# touch-24-v4.net
KiCad netlist of a schematic drawn in Altium Designer
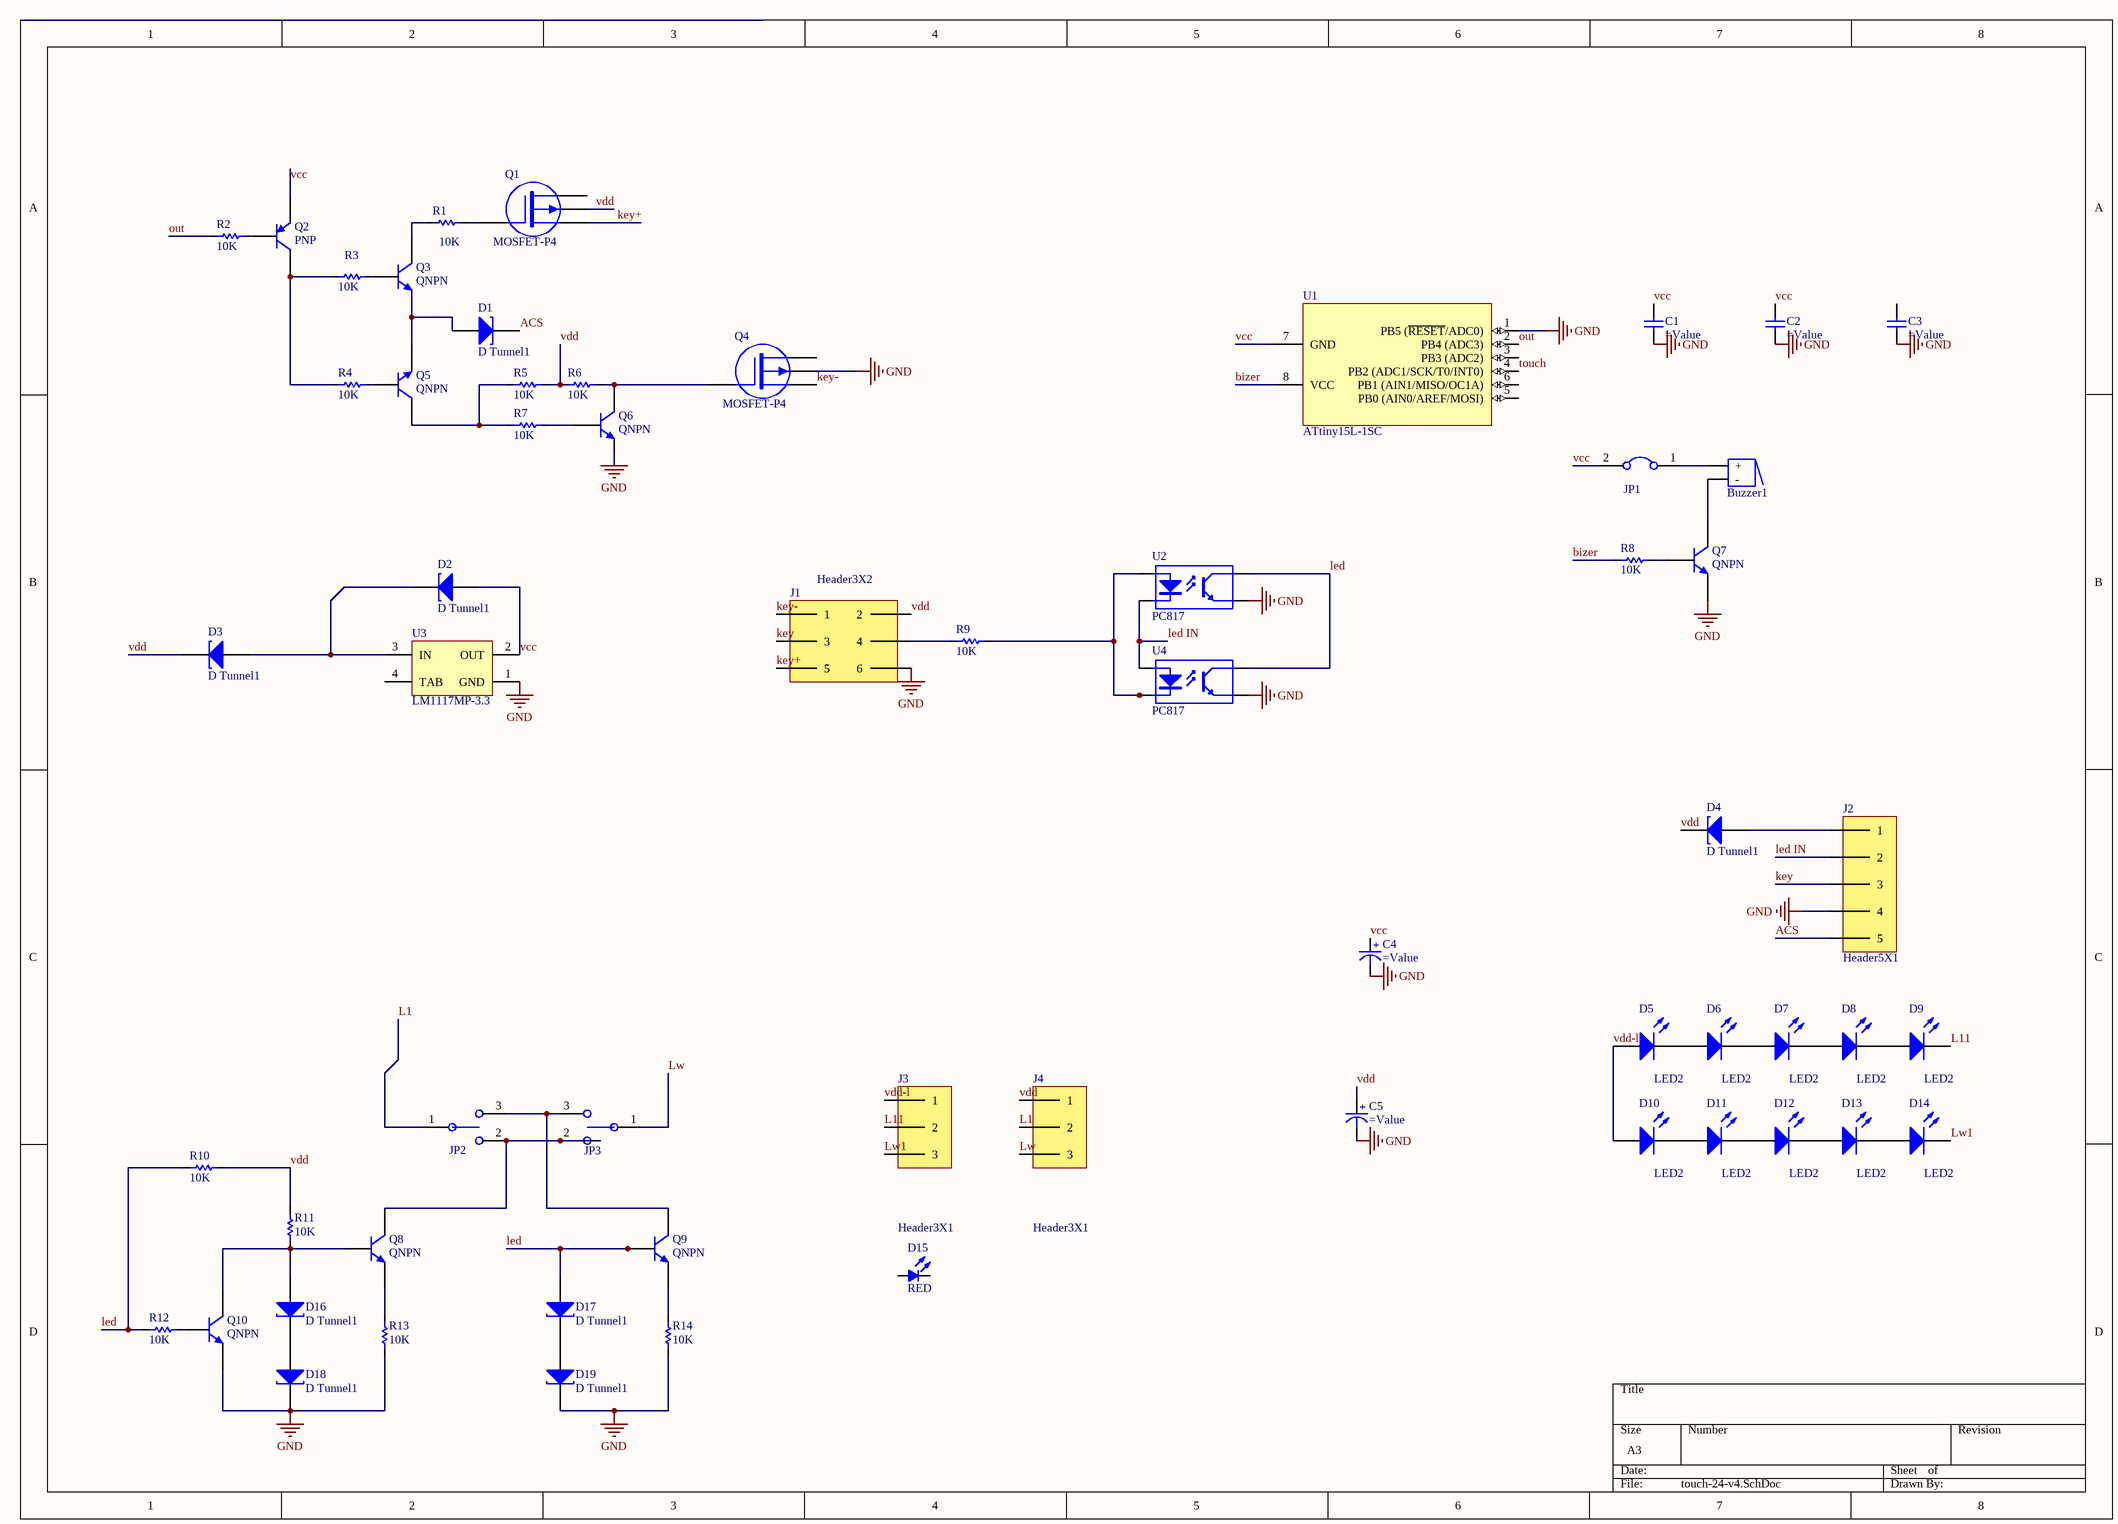
[diagram p0: touch-24-v4.SchDoc]

(export (version "E")
  (design (tool "Eeschema 10.0.6"))
  (components
    (comp (ref "Buzzer1")
      (value "Buzzer")
      (footprint "BUZZER")
      (fields (field (name "DESIGNER") "Seyed Mohsen Ghasemain"))
      (libsource (lib "PicPars.com_usefully_Library") (part "Buzzer"))
    )
    (comp (ref "C1")
      (value "~")
      (footprint "CAP 1206")
      (description "Capacitor")
      (libsource (lib "AltiumLib1") (part "Capacitor"))
    )
    (comp (ref "C2")
      (value "~")
      (footprint "CAP 1206")
      (description "Capacitor")
      (libsource (lib "AltiumLib1") (part "Capacitor"))
    )
    (comp (ref "C3")
      (value "~")
      (footprint "CAP 1206")
      (description "Capacitor")
      (libsource (lib "AltiumLib1") (part "Capacitor"))
    )
    (comp (ref "C4")
      (value "~")
      (footprint "ELEC-CAP-RAD10-20")
      (description "Electrolytic Capacitor")
      (libsource (lib "AltiumLib1") (part "Capacitor Electrolytic"))
    )
    (comp (ref "C5")
      (value "~")
      (footprint "ELEC-CAP-RAD15-30")
      (description "Electrolytic Capacitor")
      (libsource (lib "AltiumLib1") (part "Capacitor Electrolytic"))
    )
    (comp (ref "D1")
      (value "D Tunnel1")
      (footprint "3.2X1.6X1.1")
      (description "Tunnel Diode - RLC Model")
      (fields (field (name "PUBLISHER") "Altium Limited"))
      (libsource (lib "Miscellaneous Devices") (part "D Tunnel1"))
    )
    (comp (ref "D2")
      (value "D Tunnel1")
      (footprint "3.2X1.6X1.1")
      (description "Tunnel Diode - RLC Model")
      (fields (field (name "PUBLISHER") "Altium Limited"))
      (libsource (lib "Miscellaneous Devices") (part "D Tunnel1"))
    )
    (comp (ref "D3")
      (value "D Tunnel1")
      (footprint "3.2X1.6X1.1")
      (description "Tunnel Diode - RLC Model")
      (fields (field (name "PUBLISHER") "Altium Limited"))
      (libsource (lib "Miscellaneous Devices") (part "D Tunnel1"))
    )
    (comp (ref "D4")
      (value "D Tunnel1")
      (footprint "3.2X1.6X1.1")
      (description "Tunnel Diode - RLC Model")
      (fields (field (name "PUBLISHER") "Altium Limited"))
      (libsource (lib "Miscellaneous Devices") (part "D Tunnel1"))
    )
    (comp (ref "D5")
      (value "LED2")
      (footprint "3.2X1.6X1.1")
      (description "Typical RED, GREEN, YELLOW, AMBER GaAs LED")
      (fields (field (name "PUBLISHER") "Altium Limited"))
      (libsource (lib "Miscellaneous Devices") (part "LED2"))
    )
    (comp (ref "D6")
      (value "LED2")
      (footprint "3.2X1.6X1.1")
      (description "Typical RED, GREEN, YELLOW, AMBER GaAs LED")
      (fields (field (name "PUBLISHER") "Altium Limited"))
      (libsource (lib "Miscellaneous Devices") (part "LED2"))
    )
    (comp (ref "D7")
      (value "LED2")
      (footprint "3.2X1.6X1.1")
      (description "Typical RED, GREEN, YELLOW, AMBER GaAs LED")
      (fields (field (name "PUBLISHER") "Altium Limited"))
      (libsource (lib "Miscellaneous Devices") (part "LED2"))
    )
    (comp (ref "D8")
      (value "LED2")
      (footprint "3.2X1.6X1.1")
      (description "Typical RED, GREEN, YELLOW, AMBER GaAs LED")
      (fields (field (name "PUBLISHER") "Altium Limited"))
      (libsource (lib "Miscellaneous Devices") (part "LED2"))
    )
    (comp (ref "D9")
      (value "LED2")
      (footprint "3.2X1.6X1.1")
      (description "Typical RED, GREEN, YELLOW, AMBER GaAs LED")
      (fields (field (name "PUBLISHER") "Altium Limited"))
      (libsource (lib "Miscellaneous Devices") (part "LED2"))
    )
    (comp (ref "D10")
      (value "LED2")
      (footprint "3.2X1.6X1.1")
      (description "Typical RED, GREEN, YELLOW, AMBER GaAs LED")
      (fields (field (name "PUBLISHER") "Altium Limited"))
      (libsource (lib "Miscellaneous Devices") (part "LED2"))
    )
    (comp (ref "D11")
      (value "LED2")
      (footprint "3.2X1.6X1.1")
      (description "Typical RED, GREEN, YELLOW, AMBER GaAs LED")
      (fields (field (name "PUBLISHER") "Altium Limited"))
      (libsource (lib "Miscellaneous Devices") (part "LED2"))
    )
    (comp (ref "D12")
      (value "LED2")
      (footprint "3.2X1.6X1.1")
      (description "Typical RED, GREEN, YELLOW, AMBER GaAs LED")
      (fields (field (name "PUBLISHER") "Altium Limited"))
      (libsource (lib "Miscellaneous Devices") (part "LED2"))
    )
    (comp (ref "D13")
      (value "LED2")
      (footprint "3.2X1.6X1.1")
      (description "Typical RED, GREEN, YELLOW, AMBER GaAs LED")
      (fields (field (name "PUBLISHER") "Altium Limited"))
      (libsource (lib "Miscellaneous Devices") (part "LED2"))
    )
    (comp (ref "D14")
      (value "LED2")
      (footprint "3.2X1.6X1.1")
      (description "Typical RED, GREEN, YELLOW, AMBER GaAs LED")
      (fields (field (name "PUBLISHER") "Altium Limited"))
      (libsource (lib "Miscellaneous Devices") (part "LED2"))
    )
    (comp (ref "D15")
      (value "MODEL")
      (footprint "RES 0805 (2012X06L)")
      (description "Typical LED")
      (fields (field (name "COLOR") "RED"))
      (libsource (lib "AltiumLib1") (part "LED 5mm"))
    )
    (comp (ref "D16")
      (value "D Tunnel1")
      (footprint "3.2X1.6X1.1")
      (description "Tunnel Diode - RLC Model")
      (fields (field (name "PUBLISHER") "Altium Limited"))
      (libsource (lib "Miscellaneous Devices") (part "D Tunnel1"))
    )
    (comp (ref "D17")
      (value "D Tunnel1")
      (footprint "3.2X1.6X1.1")
      (description "Tunnel Diode - RLC Model")
      (fields (field (name "PUBLISHER") "Altium Limited"))
      (libsource (lib "Miscellaneous Devices") (part "D Tunnel1"))
    )
    (comp (ref "D18")
      (value "D Tunnel1")
      (footprint "3.2X1.6X1.1")
      (description "Tunnel Diode - RLC Model")
      (fields (field (name "PUBLISHER") "Altium Limited"))
      (libsource (lib "Miscellaneous Devices") (part "D Tunnel1"))
    )
    (comp (ref "D19")
      (value "D Tunnel1")
      (footprint "3.2X1.6X1.1")
      (description "Tunnel Diode - RLC Model")
      (fields (field (name "PUBLISHER") "Altium Limited"))
      (libsource (lib "Miscellaneous Devices") (part "D Tunnel1"))
    )
    (comp (ref "J1")
      (value "Header3X2")
      (footprint "HEADER 3X2")
      (libsource (lib "AltiumLib1") (part "Header3X2"))
    )
    (comp (ref "J2")
      (value "Header5X1")
      (footprint "HEADER 5X1")
      (libsource (lib "AltiumLib1") (part "Header5X1"))
    )
    (comp (ref "J3")
      (value "Header3X1")
      (footprint "HEADER 3X1")
      (libsource (lib "AltiumLib1") (part "Header3X1"))
    )
    (comp (ref "J4")
      (value "Header3X1")
      (footprint "HEADER 3X1")
      (libsource (lib "AltiumLib1") (part "Header3X1"))
    )
    (comp (ref "JP1")
      (value "Jumper")
      (footprint "Header 2X1")
      (libsource (lib "AltiumLib1") (part "Jumper"))
    )
    (comp (ref "JP2")
      (value "Jumper Selector")
      (footprint "Jumper Selector")
      (libsource (lib "AltiumLib1") (part "Jumper Selector"))
    )
    (comp (ref "JP3")
      (value "Jumper Selector")
      (footprint "Jumper Selector")
      (libsource (lib "") (part "Jumper Selector_1"))
    )
    (comp (ref "Q1")
      (value "MOSFET-P4")
      (footprint "SOT223_N")
      (description "P-Channel MOSFET, Externally Terminated Substrate")
      (fields (field (name "PUBLISHER") "Altium Limited"))
      (libsource (lib "Miscellaneous Devices") (part "MOSFET-P4"))
    )
    (comp (ref "Q2")
      (value "PNP")
      (footprint "SOT-23B_N")
      (description "PNP Bipolar Transistor")
      (fields (field (name "PUBLISHER") "Altium Limited"))
      (libsource (lib "Miscellaneous Devices") (part "PNP"))
    )
    (comp (ref "Q3")
      (value "QNPN")
      (footprint "SOT-23B_L")
      (description "NPN Bipolar Transistor")
      (fields (field (name "PUBLISHER") "Altium Limited"))
      (libsource (lib "Miscellaneous Devices") (part "QNPN"))
    )
    (comp (ref "Q4")
      (value "MOSFET-P4")
      (footprint "SOT223_N")
      (description "P-Channel MOSFET, Externally Terminated Substrate")
      (fields (field (name "PUBLISHER") "Altium Limited"))
      (libsource (lib "Miscellaneous Devices") (part "MOSFET-P4"))
    )
    (comp (ref "Q5")
      (value "QNPN")
      (footprint "SOT-23B_L")
      (description "NPN Bipolar Transistor")
      (fields (field (name "PUBLISHER") "Altium Limited"))
      (libsource (lib "Miscellaneous Devices") (part "QNPN"))
    )
    (comp (ref "Q6")
      (value "QNPN")
      (footprint "SOT-23B_L")
      (description "NPN Bipolar Transistor")
      (fields (field (name "PUBLISHER") "Altium Limited"))
      (libsource (lib "Miscellaneous Devices") (part "QNPN"))
    )
    (comp (ref "Q7")
      (value "QNPN")
      (footprint "SOT-23B_L")
      (description "NPN Bipolar Transistor")
      (fields (field (name "PUBLISHER") "Altium Limited"))
      (libsource (lib "Miscellaneous Devices") (part "QNPN"))
    )
    (comp (ref "Q8")
      (value "QNPN")
      (footprint "SOT-23B_L")
      (description "NPN Bipolar Transistor")
      (fields (field (name "PUBLISHER") "Altium Limited"))
      (libsource (lib "Miscellaneous Devices") (part "QNPN"))
    )
    (comp (ref "Q9")
      (value "QNPN")
      (footprint "SOT-23B_L")
      (description "NPN Bipolar Transistor")
      (fields (field (name "PUBLISHER") "Altium Limited"))
      (libsource (lib "Miscellaneous Devices") (part "QNPN"))
    )
    (comp (ref "Q10")
      (value "QNPN")
      (footprint "SOT-23B_L")
      (description "NPN Bipolar Transistor")
      (fields (field (name "PUBLISHER") "Altium Limited"))
      (libsource (lib "Miscellaneous Devices") (part "QNPN"))
    )
    (comp (ref "R1")
      (value "10K")
      (footprint "RES 1206 (3216X08L)")
      (description "Resistor")
      (fields (field (name "TOLERANCE") "5%") (field (name "POWER") "1/4 W"))
      (libsource (lib "AltiumLib1") (part "Resistor"))
    )
    (comp (ref "R2")
      (value "10K")
      (footprint "RES 1206 (3216X08L)")
      (description "Resistor")
      (fields (field (name "TOLERANCE") "5%") (field (name "POWER") "1/4 W"))
      (libsource (lib "AltiumLib1") (part "Resistor"))
    )
    (comp (ref "R3")
      (value "10K")
      (footprint "RES 1206 (3216X08L)")
      (description "Resistor")
      (fields (field (name "TOLERANCE") "5%") (field (name "POWER") "1/4 W"))
      (libsource (lib "AltiumLib1") (part "Resistor"))
    )
    (comp (ref "R4")
      (value "10K")
      (footprint "RES 1206 (3216X08L)")
      (description "Resistor")
      (fields (field (name "TOLERANCE") "5%") (field (name "POWER") "1/4 W"))
      (libsource (lib "AltiumLib1") (part "Resistor"))
    )
    (comp (ref "R5")
      (value "10K")
      (footprint "RES 1206 (3216X08L)")
      (description "Resistor")
      (fields (field (name "TOLERANCE") "5%") (field (name "POWER") "1/4 W"))
      (libsource (lib "AltiumLib1") (part "Resistor"))
    )
    (comp (ref "R6")
      (value "10K")
      (footprint "RES 1206 (3216X08L)")
      (description "Resistor")
      (fields (field (name "TOLERANCE") "5%") (field (name "POWER") "1/4 W"))
      (libsource (lib "AltiumLib1") (part "Resistor"))
    )
    (comp (ref "R7")
      (value "10K")
      (footprint "RES 1206 (3216X08L)")
      (description "Resistor")
      (fields (field (name "TOLERANCE") "5%") (field (name "POWER") "1/4 W"))
      (libsource (lib "AltiumLib1") (part "Resistor"))
    )
    (comp (ref "R8")
      (value "10K")
      (footprint "RES 1206 (3216X08L)")
      (description "Resistor")
      (fields (field (name "TOLERANCE") "5%") (field (name "POWER") "1/4 W"))
      (libsource (lib "AltiumLib1") (part "Resistor"))
    )
    (comp (ref "R9")
      (value "10K")
      (footprint "RES 1206 (3216X08L)")
      (description "Resistor")
      (fields (field (name "TOLERANCE") "5%") (field (name "POWER") "1/4 W"))
      (libsource (lib "AltiumLib1") (part "Resistor"))
    )
    (comp (ref "R10")
      (value "10K")
      (footprint "RES 1206 (3216X08L)")
      (description "Resistor")
      (fields (field (name "TOLERANCE") "5%") (field (name "POWER") "1/4 W"))
      (libsource (lib "AltiumLib1") (part "Resistor"))
    )
    (comp (ref "R11")
      (value "10K")
      (footprint "RES 1206 (3216X08L)")
      (description "Resistor")
      (fields (field (name "TOLERANCE") "5%") (field (name "POWER") "1/4 W"))
      (libsource (lib "AltiumLib1") (part "Resistor"))
    )
    (comp (ref "R12")
      (value "10K")
      (footprint "RES 1206 (3216X08L)")
      (description "Resistor")
      (fields (field (name "TOLERANCE") "5%") (field (name "POWER") "1/4 W"))
      (libsource (lib "AltiumLib1") (part "Resistor"))
    )
    (comp (ref "R13")
      (value "10K")
      (footprint "RES 1206 (3216X08L)")
      (description "Resistor")
      (fields (field (name "TOLERANCE") "5%") (field (name "POWER") "1/4 W"))
      (libsource (lib "AltiumLib1") (part "Resistor"))
    )
    (comp (ref "R14")
      (value "10K")
      (footprint "RES 1206 (3216X08L)")
      (description "Resistor")
      (fields (field (name "TOLERANCE") "5%") (field (name "POWER") "1/4 W"))
      (libsource (lib "AltiumLib1") (part "Resistor"))
    )
    (comp (ref "U1")
      (value "ATtiny15L-1SC")
      (footprint "8S2_N")
      (description "8-Bit AVR Microcontroller with 1K Byte of Flash Memory")
      (fields (field (name "PUBLISHER") "Altium Limited"))
      (libsource (lib "Atmel Microcontroller 8-Bit AVR") (part "ATtiny15L-1SC"))
    )
    (comp (ref "U2")
      (value "PC817")
      (footprint "DIP4")
      (description "4-Pin Phototransistor Optocoupler")
      (libsource (lib "AltiumLib1") (part "OPTCOUPLER_01"))
    )
    (comp (ref "U3")
      (value "LM1117MP-3.3")
      (footprint "Miscellaneous Devices:SOT89L")
      (description "800mA Low-Dropout Linear Regulator")
      (fields
        (field (name "MANUFACTURER") "National Semiconductor")
        (field (name "DIGIKEYPARTNUMBER") "LM1117MP-3.3CT-ND")
        (field (name "PUBLISHER") "Altium Limited")
      )
      (libsource (lib "NSC LDO") (part "LM1117MP-3.3"))
    )
    (comp (ref "U4")
      (value "PC817")
      (footprint "DIP4")
      (description "4-Pin Phototransistor Optocoupler")
      (libsource (lib "AltiumLib1") (part "OPTCOUPLER_01"))
    )
  )
  (nets
    (net (code "1") (name "/ACS") (class "Default")
      (node (ref "D1") (pin "2") (pinfunction "K_2") (pintype "passive"))
      (node (ref "J2") (pin "5") (pinfunction "5_5") (pintype "passive"))
    )
    (net (code "2") (name "/L1") (class "Default")
      (node (ref "J4") (pin "2") (pinfunction "2_2") (pintype "passive"))
      (node (ref "JP2") (pin "1") (pinfunction "1_1") (pintype "passive"))
    )
    (net (code "3") (name "/L11") (class "Default")
      (node (ref "D9") (pin "2") (pinfunction "K_2") (pintype "passive"))
      (node (ref "J3") (pin "2") (pinfunction "2_2") (pintype "passive"))
    )
    (net (code "4") (name "/Lw") (class "Default")
      (node (ref "J4") (pin "3") (pinfunction "3_3") (pintype "passive"))
      (node (ref "JP3") (pin "1") (pinfunction "1_1") (pintype "passive"))
    )
    (net (code "5") (name "/Lw1") (class "Default")
      (node (ref "D14") (pin "2") (pinfunction "K_2") (pintype "passive"))
      (node (ref "J3") (pin "3") (pinfunction "3_3") (pintype "passive"))
    )
    (net (code "6") (name "/bizer") (class "Default")
      (node (ref "R8") (pin "1") (pinfunction "1_1") (pintype "passive"))
      (node (ref "U1") (pin "8") (pinfunction "VCC_8") (pintype "power_in"))
    )
    (net (code "7") (name "/key") (class "Default")
      (node (ref "J1") (pin "3") (pinfunction "3_3") (pintype "passive"))
      (node (ref "J2") (pin "3") (pinfunction "3_3") (pintype "passive"))
    )
    (net (code "8") (name "/key+") (class "Default")
      (node (ref "J1") (pin "5") (pinfunction "5_5") (pintype "passive"))
      (node (ref "Q1") (pin "4") (pinfunction "S_4") (pintype "passive"))
    )
    (net (code "9") (name "/key-") (class "Default")
      (node (ref "J1") (pin "1") (pinfunction "1_1") (pintype "passive"))
      (node (ref "Q4") (pin "4") (pinfunction "S_4") (pintype "passive"))
    )
    (net (code "10") (name "/led") (class "Default")
      (node (ref "D17") (pin "1") (pinfunction "A_1") (pintype "passive"))
      (node (ref "Q9") (pin "2") (pinfunction "B_2") (pintype "passive"))
      (node (ref "R10") (pin "1") (pinfunction "1_1") (pintype "passive"))
      (node (ref "R12") (pin "1") (pinfunction "1_1") (pintype "passive"))
      (node (ref "U2") (pin "4") (pinfunction "C_4") (pintype "passive"))
      (node (ref "U4") (pin "4") (pinfunction "C_4") (pintype "passive"))
    )
    (net (code "11") (name "/led IN") (class "Default")
      (node (ref "J2") (pin "2") (pinfunction "2_2") (pintype "passive"))
      (node (ref "U2") (pin "2") (pinfunction "K_2") (pintype "passive"))
      (node (ref "U4") (pin "1") (pinfunction "A_1") (pintype "passive"))
    )
    (net (code "12") (name "/out") (class "Default")
      (node (ref "R2") (pin "1") (pinfunction "1_1") (pintype "passive"))
      (node (ref "U1") (pin "2") (pinfunction "PB4_(ADC3)_2") (pintype "bidirectional"))
    )
    (net (code "13") (name "/touch") (class "Default")
      (node (ref "U1") (pin "4") (pinfunction "PB2_(ADC1/SCK/T0/INT0)_4") (pintype "bidirectional"))
    )
    (net (code "14") (name "/vcc") (class "Default")
      (node (ref "C1") (pin "2") (pinfunction "-_2") (pintype "passive"))
      (node (ref "C2") (pin "2") (pinfunction "-_2") (pintype "passive"))
      (node (ref "C4") (pin "2") (pinfunction "+_2") (pintype "passive"))
      (node (ref "D2") (pin "1") (pinfunction "A_1") (pintype "passive"))
      (node (ref "JP1") (pin "2") (pinfunction "2_2") (pintype "passive"))
      (node (ref "Q2") (pin "3") (pinfunction "E_3") (pintype "passive"))
      (node (ref "U1") (pin "7") (pinfunction "GND_7") (pintype "power_in"))
      (node (ref "U3") (pin "2") (pinfunction "OUT_2") (pintype "power_in"))
    )
    (net (code "15") (name "/vdd") (class "Default")
      (node (ref "C5") (pin "2") (pinfunction "+_2") (pintype "passive"))
      (node (ref "D3") (pin "2") (pinfunction "K_2") (pintype "passive"))
      (node (ref "D4") (pin "2") (pinfunction "K_2") (pintype "passive"))
      (node (ref "J1") (pin "2") (pinfunction "2_2") (pintype "passive"))
      (node (ref "J4") (pin "1") (pinfunction "1_1") (pintype "passive"))
      (node (ref "Q1") (pin "3") (pinfunction "U_3") (pintype "passive"))
      (node (ref "R10") (pin "2") (pinfunction "2_2") (pintype "passive"))
      (node (ref "R11") (pin "2") (pinfunction "2_2") (pintype "passive"))
      (node (ref "R5") (pin "2") (pinfunction "2_2") (pintype "passive"))
      (node (ref "R6") (pin "1") (pinfunction "1_1") (pintype "passive"))
    )
    (net (code "16") (name "/vdd-l") (class "Default")
      (node (ref "D10") (pin "1") (pinfunction "A_1") (pintype "passive"))
      (node (ref "D5") (pin "1") (pinfunction "A_1") (pintype "passive"))
      (node (ref "J3") (pin "1") (pinfunction "1_1") (pintype "passive"))
    )
    (net (code "17") (name "GND") (class "Default")
      (node (ref "C1") (pin "1") (pinfunction "+_1") (pintype "passive"))
      (node (ref "C2") (pin "1") (pinfunction "+_1") (pintype "passive"))
      (node (ref "C3") (pin "1") (pinfunction "+_1") (pintype "passive"))
      (node (ref "C4") (pin "1") (pinfunction "-_1") (pintype "passive"))
      (node (ref "C5") (pin "1") (pinfunction "-_1") (pintype "passive"))
      (node (ref "D18") (pin "2") (pinfunction "K_2") (pintype "passive"))
      (node (ref "D19") (pin "2") (pinfunction "K_2") (pintype "passive"))
      (node (ref "J1") (pin "6") (pinfunction "6_6") (pintype "passive"))
      (node (ref "J2") (pin "4") (pinfunction "4_4") (pintype "passive"))
      (node (ref "Q10") (pin "3") (pinfunction "E_3") (pintype "passive"))
      (node (ref "Q4") (pin "3") (pinfunction "U_3") (pintype "passive"))
      (node (ref "Q6") (pin "3") (pinfunction "E_3") (pintype "passive"))
      (node (ref "Q7") (pin "3") (pinfunction "E_3") (pintype "passive"))
      (node (ref "R13") (pin "1") (pinfunction "1_1") (pintype "passive"))
      (node (ref "R14") (pin "1") (pinfunction "1_1") (pintype "passive"))
      (node (ref "U1") (pin "1") (pinfunction "PB5_(~{RESET}/ADC0)_1") (pintype "bidirectional"))
      (node (ref "U2") (pin "3") (pinfunction "E_3") (pintype "passive"))
      (node (ref "U3") (pin "1") (pinfunction "GND_1") (pintype "power_in"))
      (node (ref "U4") (pin "3") (pinfunction "E_3") (pintype "passive"))
    )
    (net (code "18") (name "Net-(Buzzer1-+)") (class "Default")
      (node (ref "Buzzer1") (pin "1") (pinfunction "+_1") (pintype "passive"))
      (node (ref "JP1") (pin "1") (pinfunction "1_1") (pintype "passive"))
    )
    (net (code "19") (name "Net-(Buzzer1--)") (class "Default")
      (node (ref "Buzzer1") (pin "2") (pinfunction "-_2") (pintype "passive"))
      (node (ref "Q7") (pin "1") (pinfunction "C_1") (pintype "passive"))
    )
    (net (code "20") (name "Net-(D1-A)") (class "Default")
      (node (ref "D1") (pin "1") (pinfunction "A_1") (pintype "passive"))
      (node (ref "Q3") (pin "3") (pinfunction "E_3") (pintype "passive"))
      (node (ref "Q5") (pin "3") (pinfunction "E_3") (pintype "passive"))
    )
    (net (code "21") (name "Net-(D2-K)") (class "Default")
      (node (ref "D2") (pin "2") (pinfunction "K_2") (pintype "passive"))
      (node (ref "D3") (pin "1") (pinfunction "A_1") (pintype "passive"))
      (node (ref "U3") (pin "3") (pinfunction "IN_3") (pintype "power_in"))
    )
    (net (code "22") (name "Net-(D4-A)") (class "Default")
      (node (ref "D4") (pin "1") (pinfunction "A_1") (pintype "passive"))
      (node (ref "J2") (pin "1") (pinfunction "1_1") (pintype "passive"))
    )
    (net (code "23") (name "Net-(D5-K)") (class "Default")
      (node (ref "D5") (pin "2") (pinfunction "K_2") (pintype "passive"))
      (node (ref "D6") (pin "1") (pinfunction "A_1") (pintype "passive"))
    )
    (net (code "24") (name "Net-(D6-K)") (class "Default")
      (node (ref "D6") (pin "2") (pinfunction "K_2") (pintype "passive"))
      (node (ref "D7") (pin "1") (pinfunction "A_1") (pintype "passive"))
    )
    (net (code "25") (name "Net-(D7-K)") (class "Default")
      (node (ref "D7") (pin "2") (pinfunction "K_2") (pintype "passive"))
      (node (ref "D8") (pin "1") (pinfunction "A_1") (pintype "passive"))
    )
    (net (code "26") (name "Net-(D8-K)") (class "Default")
      (node (ref "D8") (pin "2") (pinfunction "K_2") (pintype "passive"))
      (node (ref "D9") (pin "1") (pinfunction "A_1") (pintype "passive"))
    )
    (net (code "27") (name "Net-(D10-K)") (class "Default")
      (node (ref "D10") (pin "2") (pinfunction "K_2") (pintype "passive"))
      (node (ref "D11") (pin "1") (pinfunction "A_1") (pintype "passive"))
    )
    (net (code "28") (name "Net-(D11-K)") (class "Default")
      (node (ref "D11") (pin "2") (pinfunction "K_2") (pintype "passive"))
      (node (ref "D12") (pin "1") (pinfunction "A_1") (pintype "passive"))
    )
    (net (code "29") (name "Net-(D12-K)") (class "Default")
      (node (ref "D12") (pin "2") (pinfunction "K_2") (pintype "passive"))
      (node (ref "D13") (pin "1") (pinfunction "A_1") (pintype "passive"))
    )
    (net (code "30") (name "Net-(D13-K)") (class "Default")
      (node (ref "D13") (pin "2") (pinfunction "K_2") (pintype "passive"))
      (node (ref "D14") (pin "1") (pinfunction "A_1") (pintype "passive"))
    )
    (net (code "31") (name "Net-(D16-A)") (class "Default")
      (node (ref "D16") (pin "1") (pinfunction "A_1") (pintype "passive"))
      (node (ref "Q10") (pin "1") (pinfunction "C_1") (pintype "passive"))
      (node (ref "Q8") (pin "2") (pinfunction "B_2") (pintype "passive"))
      (node (ref "R11") (pin "1") (pinfunction "1_1") (pintype "passive"))
    )
    (net (code "32") (name "Net-(D16-K)") (class "Default")
      (node (ref "D16") (pin "2") (pinfunction "K_2") (pintype "passive"))
      (node (ref "D18") (pin "1") (pinfunction "A_1") (pintype "passive"))
    )
    (net (code "33") (name "Net-(D17-K)") (class "Default")
      (node (ref "D17") (pin "2") (pinfunction "K_2") (pintype "passive"))
      (node (ref "D19") (pin "1") (pinfunction "A_1") (pintype "passive"))
    )
    (net (code "34") (name "Net-(J1-Pad4)") (class "Default")
      (node (ref "J1") (pin "4") (pinfunction "4_4") (pintype "passive"))
      (node (ref "R9") (pin "1") (pinfunction "1_1") (pintype "passive"))
    )
    (net (code "35") (name "Net-(Q1-G)") (class "Default")
      (node (ref "Q1") (pin "1") (pinfunction "G_1") (pintype "passive"))
      (node (ref "R1") (pin "2") (pinfunction "2_2") (pintype "passive"))
    )
    (net (code "36") (name "Net-(Q2-B)") (class "Default")
      (node (ref "Q2") (pin "2") (pinfunction "B_2") (pintype "passive"))
      (node (ref "R2") (pin "2") (pinfunction "2_2") (pintype "passive"))
    )
    (net (code "37") (name "Net-(Q2-C)") (class "Default")
      (node (ref "Q2") (pin "1") (pinfunction "C_1") (pintype "passive"))
      (node (ref "R3") (pin "1") (pinfunction "1_1") (pintype "passive"))
      (node (ref "R4") (pin "1") (pinfunction "1_1") (pintype "passive"))
    )
    (net (code "38") (name "Net-(Q3-B)") (class "Default")
      (node (ref "Q3") (pin "2") (pinfunction "B_2") (pintype "passive"))
      (node (ref "R3") (pin "2") (pinfunction "2_2") (pintype "passive"))
    )
    (net (code "39") (name "Net-(Q3-C)") (class "Default")
      (node (ref "Q3") (pin "1") (pinfunction "C_1") (pintype "passive"))
      (node (ref "R1") (pin "1") (pinfunction "1_1") (pintype "passive"))
    )
    (net (code "40") (name "Net-(Q4-G)") (class "Default")
      (node (ref "Q4") (pin "1") (pinfunction "G_1") (pintype "passive"))
      (node (ref "Q6") (pin "1") (pinfunction "C_1") (pintype "passive"))
      (node (ref "R6") (pin "2") (pinfunction "2_2") (pintype "passive"))
    )
    (net (code "41") (name "Net-(Q5-B)") (class "Default")
      (node (ref "Q5") (pin "2") (pinfunction "B_2") (pintype "passive"))
      (node (ref "R4") (pin "2") (pinfunction "2_2") (pintype "passive"))
    )
    (net (code "42") (name "Net-(Q5-C)") (class "Default")
      (node (ref "Q5") (pin "1") (pinfunction "C_1") (pintype "passive"))
      (node (ref "R5") (pin "1") (pinfunction "1_1") (pintype "passive"))
      (node (ref "R7") (pin "1") (pinfunction "1_1") (pintype "passive"))
    )
    (net (code "43") (name "Net-(Q6-B)") (class "Default")
      (node (ref "Q6") (pin "2") (pinfunction "B_2") (pintype "passive"))
      (node (ref "R7") (pin "2") (pinfunction "2_2") (pintype "passive"))
    )
    (net (code "44") (name "Net-(Q7-B)") (class "Default")
      (node (ref "Q7") (pin "2") (pinfunction "B_2") (pintype "passive"))
      (node (ref "R8") (pin "2") (pinfunction "2_2") (pintype "passive"))
    )
    (net (code "45") (name "Net-(Q8-C)") (class "Default")
      (node (ref "JP2") (pin "2") (pinfunction "2_2") (pintype "passive"))
      (node (ref "JP3") (pin "2") (pinfunction "2_2") (pintype "passive"))
      (node (ref "Q8") (pin "1") (pinfunction "C_1") (pintype "passive"))
    )
    (net (code "46") (name "Net-(Q8-E)") (class "Default")
      (node (ref "Q8") (pin "3") (pinfunction "E_3") (pintype "passive"))
      (node (ref "R13") (pin "2") (pinfunction "2_2") (pintype "passive"))
    )
    (net (code "47") (name "Net-(Q9-C)") (class "Default")
      (node (ref "JP2") (pin "3") (pinfunction "3_3") (pintype "passive"))
      (node (ref "JP3") (pin "3") (pinfunction "3_3") (pintype "passive"))
      (node (ref "Q9") (pin "1") (pinfunction "C_1") (pintype "passive"))
    )
    (net (code "48") (name "Net-(Q9-E)") (class "Default")
      (node (ref "Q9") (pin "3") (pinfunction "E_3") (pintype "passive"))
      (node (ref "R14") (pin "2") (pinfunction "2_2") (pintype "passive"))
    )
    (net (code "49") (name "Net-(Q10-B)") (class "Default")
      (node (ref "Q10") (pin "2") (pinfunction "B_2") (pintype "passive"))
      (node (ref "R12") (pin "2") (pinfunction "2_2") (pintype "passive"))
    )
    (net (code "50") (name "Net-(U2-A)") (class "Default")
      (node (ref "R9") (pin "2") (pinfunction "2_2") (pintype "passive"))
      (node (ref "U2") (pin "1") (pinfunction "A_1") (pintype "passive"))
      (node (ref "U4") (pin "2") (pinfunction "K_2") (pintype "passive"))
    )
    (net (code "51") (name "unconnected-(C3---Pad2)") (class "Default")
      (node (ref "C3") (pin "2") (pinfunction "-_2") (pintype "passive"))
    )
    (net (code "52") (name "unconnected-(D15-A-Pad1)") (class "Default")
      (node (ref "D15") (pin "1") (pinfunction "A_1") (pintype "passive"))
    )
    (net (code "53") (name "unconnected-(D15-K-Pad2)") (class "Default")
      (node (ref "D15") (pin "2") (pinfunction "K_2") (pintype "passive"))
    )
    (net (code "54") (name "unconnected-(Q1-D-Pad2)") (class "Default")
      (node (ref "Q1") (pin "2") (pinfunction "D_2") (pintype "passive"))
    )
    (net (code "55") (name "unconnected-(Q4-D-Pad2)") (class "Default")
      (node (ref "Q4") (pin "2") (pinfunction "D_2") (pintype "passive"))
    )
    (net (code "56") (name "unconnected-(U1-PB0_(AIN0{slash}AREF{slash}MOSI)-Pad5)") (class "Default")
      (node (ref "U1") (pin "5") (pinfunction "PB0_(AIN0/AREF/MOSI)_5") (pintype "bidirectional"))
    )
    (net (code "57") (name "unconnected-(U1-PB1_(AIN1{slash}MISO{slash}OC1A)-Pad6)") (class "Default")
      (node (ref "U1") (pin "6") (pinfunction "PB1_(AIN1/MISO/OC1A)_6") (pintype "bidirectional"))
    )
    (net (code "58") (name "unconnected-(U1-PB3_(ADC2)-Pad3)") (class "Default")
      (node (ref "U1") (pin "3") (pinfunction "PB3_(ADC2)_3") (pintype "bidirectional"))
    )
    (net (code "59") (name "unconnected-(U3-TAB-Pad4)") (class "Default")
      (node (ref "U3") (pin "4") (pinfunction "TAB_4") (pintype "power_in"))
    )
  )
)
